# Power.net
KiCad netlist of a schematic drawn in Altium Designer
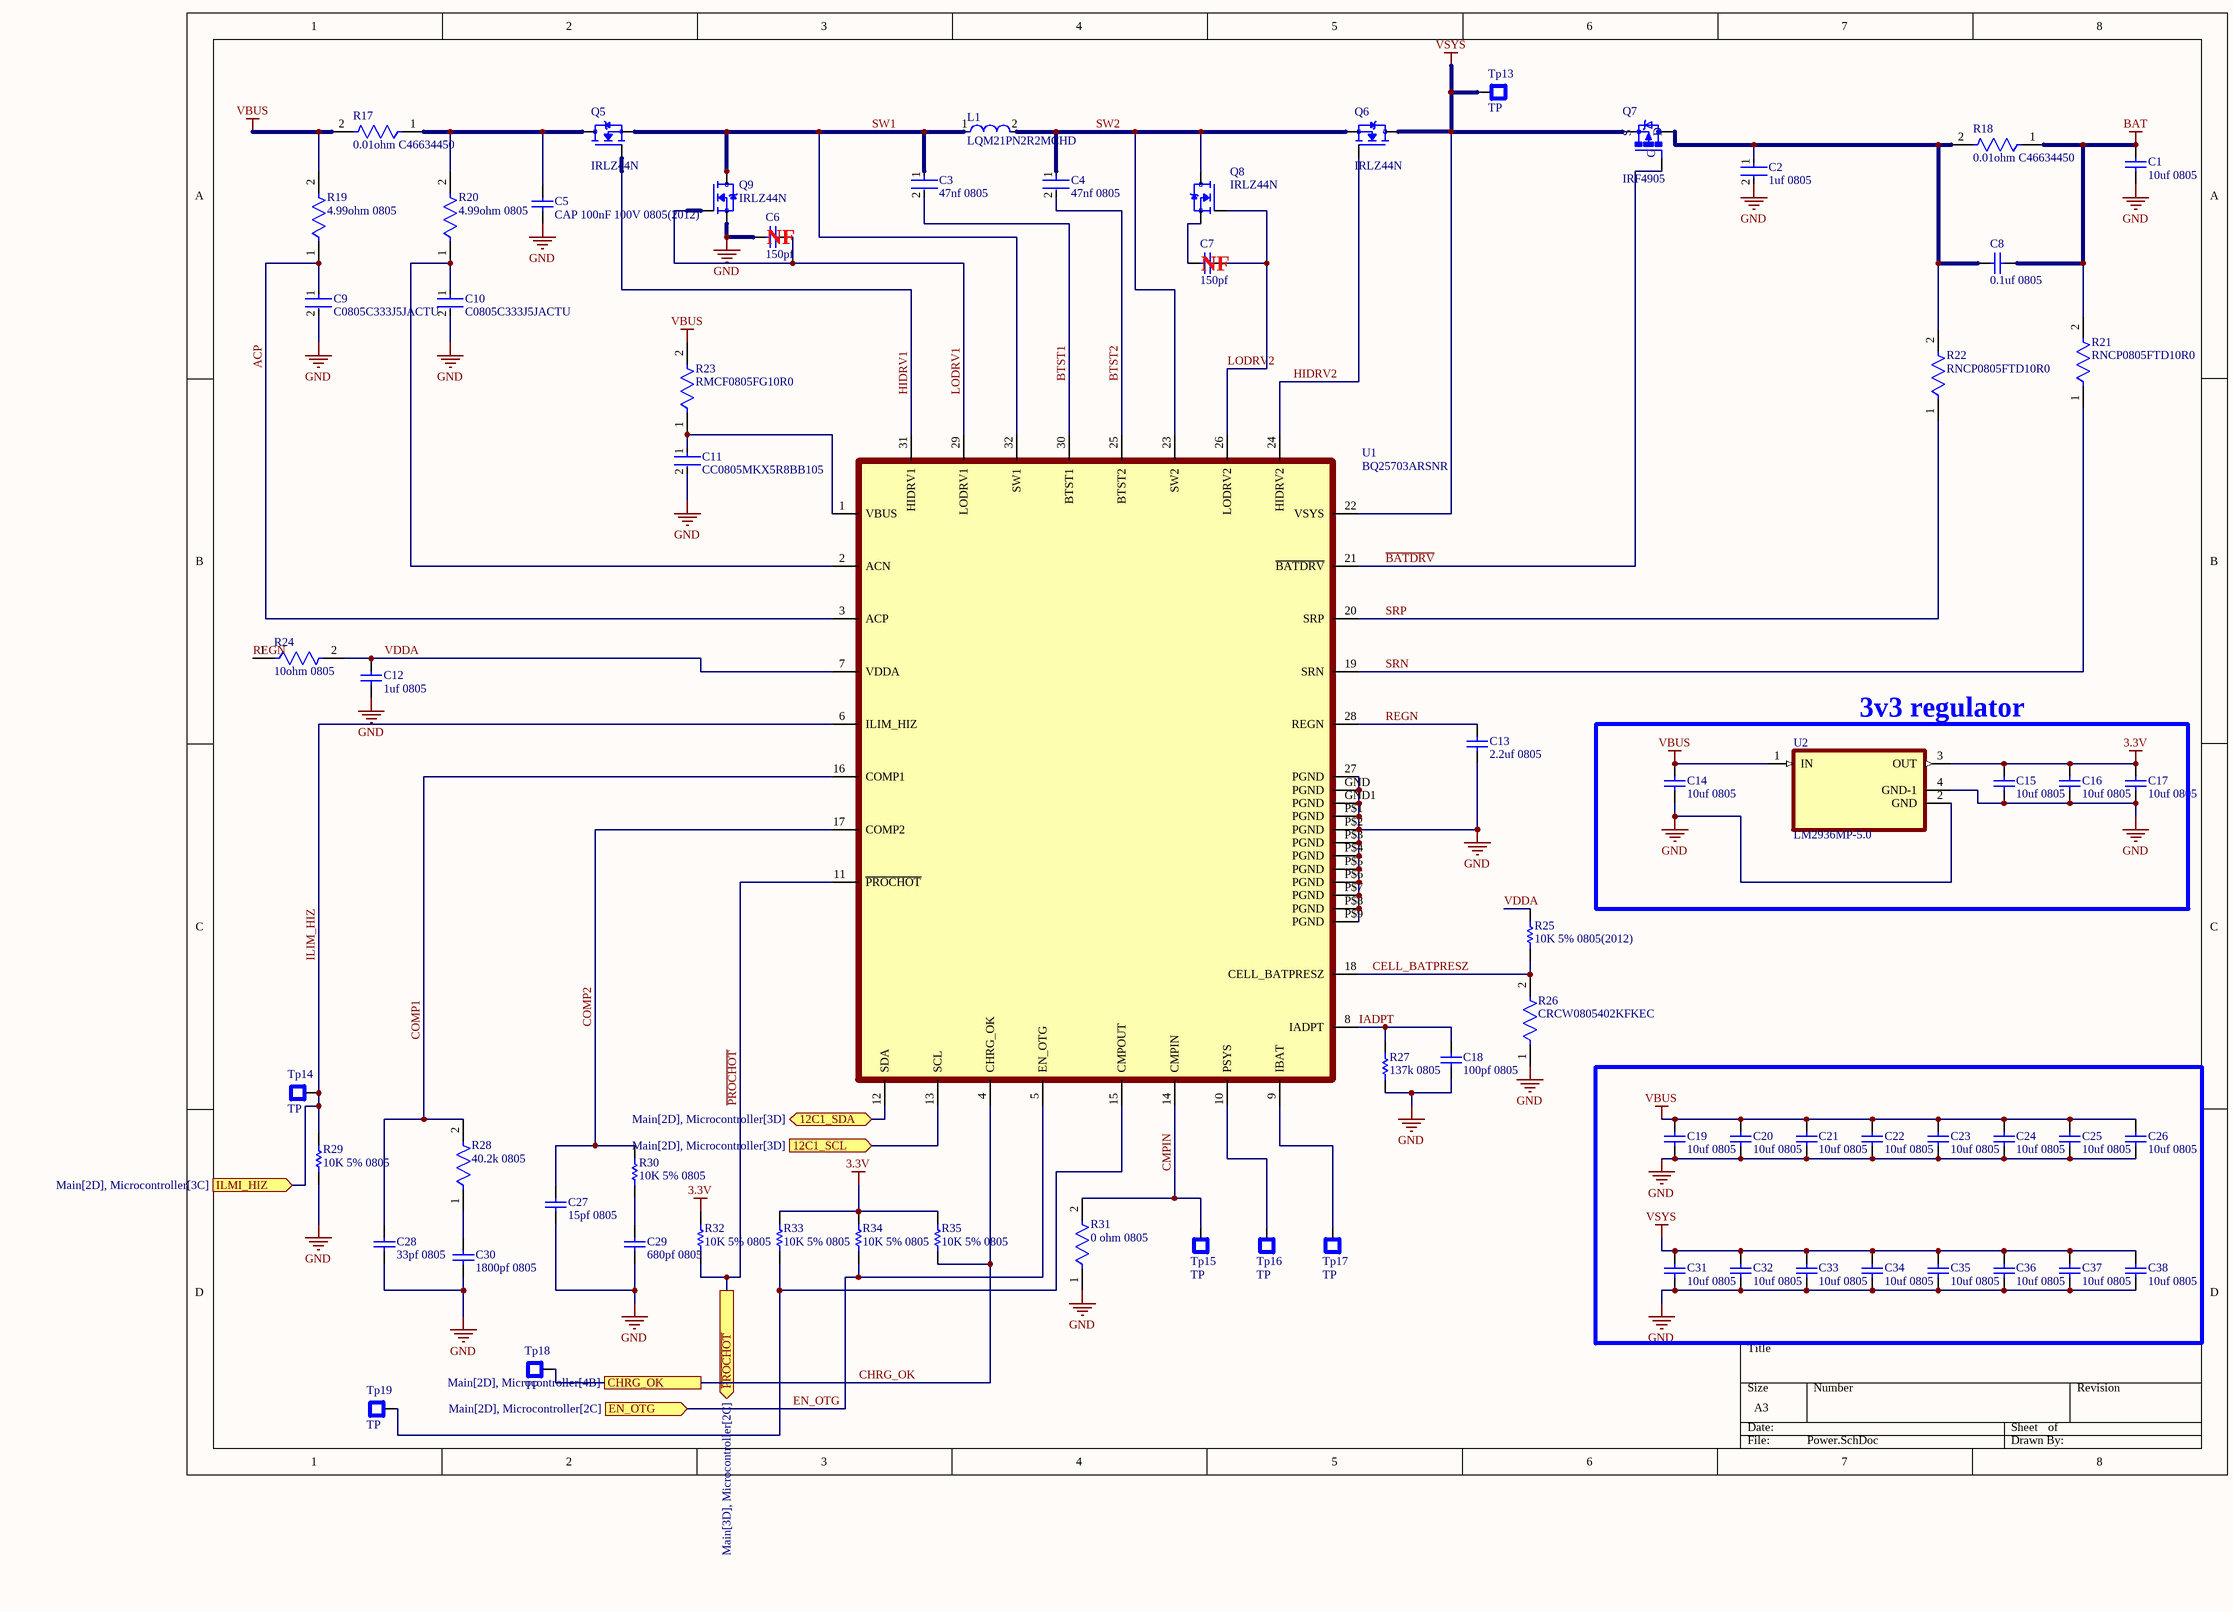
[diagram p0: Power.SchDoc]

(export (version "E")
  (design (tool "Eeschema 10.0.6"))
  (components
    (comp (ref "C1")
      (value "10uf 0805")
      (footprint "CAPC2013X140X50ML20T25")
      (fields
        (field (name "MANUFACTURER") "AVX Interconnect / Elco")
        (field (name "PART NUMBER") "0805ZC106KAT2A")
      )
      (libsource (lib "Altium Content Vault") (part "CAP"))
    )
    (comp (ref "C2")
      (value "1uf 0805")
      (footprint "FP-0805-L_2_01_0_2-W_1_25-MFG")
      (description "08051C105K4T2A Cap Ceramic 1uF 100V X7R 10% Pad SMD 0805 125C Automotive T/R")
      (fields (field (name "TOLERANCE") "10%"))
      (libsource (lib "Altium Content Vault") (part "b4654b650e69147ec39a6b967a45e02"))
    )
    (comp (ref "C3")
      (value "47nf 0805")
      (footprint "FP-C0805C-DN-MFG")
      (description "CAP CER 0.047UF 50V X7R 0805")
      (fields (field (name "TOLERANCE") "0.1") (field (name "MANUFACTURER") "KEMET"))
      (libsource (lib "Altium Content Vault") (part "b4654b650e69147ec39a6b967a45e02"))
    )
    (comp (ref "C4")
      (value "47nf 0805")
      (footprint "FP-C0805C-DN-MFG")
      (description "CAP CER 0.047UF 50V X7R 0805")
      (fields (field (name "TOLERANCE") "0.1") (field (name "MANUFACTURER") "KEMET"))
      (libsource (lib "Altium Content Vault") (part "b4654b650e69147ec39a6b967a45e02"))
    )
    (comp (ref "C5")
      (value "CAP 100nF 100V 0805(2012)")
      (footprint "CAPC0805(2012)145_M")
      (description "CAP 100nF 100V ±10% 0805 (2012 Metric) Thickness 1.45mm SMD")
      (fields (field (name "TOLERANCE") "Â±10%"))
      (libsource (lib "Altium Content Vault") (part "CAP"))
    )
    (comp (ref "C6")
      (value "150pf")
      (footprint "CAPC2013X145X48NL20T23")
      (fields (field (name "PART NUMBER") "VJ0805A151JXAMC") (field (name "MANUFACTURER") "Vitramon"))
      (libsource (lib "Altium Content Vault") (part "CAP"))
    )
    (comp (ref "C7")
      (value "150pf")
      (footprint "CAPC2013X145X48NL20T23")
      (fields (field (name "PART NUMBER") "VJ0805A151JXAMC") (field (name "MANUFACTURER") "Vitramon"))
      (libsource (lib "Altium Content Vault") (part "CAP"))
    )
    (comp (ref "C8")
      (value "0.1uf 0805")
      (footprint "CAPC2013X140X50ML20T25")
      (fields
        (field (name "PART NUMBER") "0805DD104KAT2A")
        (field (name "MANUFACTURER") "AVX Interconnect / Elco")
      )
      (libsource (lib "Altium Content Vault") (part "CAP"))
    )
    (comp (ref "C9")
      (value "C0805C333J5JACTU")
      (footprint "FP-C0805C-DN-MFG")
      (description "CAP CER 0.033UF 50V U2J 0805")
      (fields
        (field (name "MANUFACTURER") "KEMET")
        (field (name "OCTOPART") "https://octopart.com/c0805c333j5jactu-kemet-74774612")
      )
      (libsource (lib "Altium Content Vault") (part "b4654b650e69147ec39a6b967a45e02"))
    )
    (comp (ref "C10")
      (value "C0805C333J5JACTU")
      (footprint "FP-C0805C-DN-MFG")
      (description "CAP CER 0.033UF 50V U2J 0805")
      (fields
        (field (name "MANUFACTURER") "KEMET")
        (field (name "OCTOPART") "https://octopart.com/c0805c333j5jactu-kemet-74774612")
      )
      (libsource (lib "Altium Content Vault") (part "b4654b650e69147ec39a6b967a45e02"))
    )
    (comp (ref "C11")
      (value "CC0805MKX5R8BB105")
      (footprint "FP-CC0805-0_85-MFG")
      (description "CAP CER 1UF 25V X5R 0805")
      (fields
        (field (name "MANUFACTURER") "Yageo")
        (field (name "OCTOPART") "https://octopart.com/cc0805mkx5r8bb105-yageo-81932645")
      )
      (libsource (lib "Altium Content Vault") (part "11868f565c42a9108669ba33697ecf6"))
    )
    (comp (ref "C12")
      (value "1uf 0805")
      (footprint "CAPC2013X145X50NL20T20")
      (fields (field (name "PART NUMBER") "VJ0805Y105KXQRW1BC") (field (name "MANUFACTURER") "Vitramon"))
      (libsource (lib "Altium Content Vault") (part "CAP"))
    )
    (comp (ref "C13")
      (value "2.2uf 0805")
      (footprint "CAPC2013X100X50ML20T25")
      (fields (field (name "PART NUMBER") "C0805C225M4PACTU") (field (name "MANUFACTURER") "Kemet"))
      (libsource (lib "Altium Content Vault") (part "CAP"))
    )
    (comp (ref "C14")
      (value "10uf 0805")
      (footprint "CAPC2013X140X50ML20T25")
      (fields
        (field (name "MANUFACTURER") "AVX Interconnect / Elco")
        (field (name "PART NUMBER") "0805ZC106KAT2A")
      )
      (libsource (lib "Altium Content Vault") (part "CAP"))
    )
    (comp (ref "C15")
      (value "10uf 0805")
      (footprint "CAPC2013X140X50ML20T25")
      (fields
        (field (name "MANUFACTURER") "AVX Interconnect / Elco")
        (field (name "PART NUMBER") "0805ZC106KAT2A")
      )
      (libsource (lib "Altium Content Vault") (part "CAP"))
    )
    (comp (ref "C16")
      (value "10uf 0805")
      (footprint "CAPC2013X140X50ML20T25")
      (fields
        (field (name "MANUFACTURER") "AVX Interconnect / Elco")
        (field (name "PART NUMBER") "0805ZC106KAT2A")
      )
      (libsource (lib "Altium Content Vault") (part "CAP"))
    )
    (comp (ref "C17")
      (value "10uf 0805")
      (footprint "CAPC2013X140X50ML20T25")
      (fields
        (field (name "MANUFACTURER") "AVX Interconnect / Elco")
        (field (name "PART NUMBER") "0805ZC106KAT2A")
      )
      (libsource (lib "Altium Content Vault") (part "CAP"))
    )
    (comp (ref "C18")
      (value "100pf 0805")
      (footprint "CAPC2013X127X50NL20T25")
      (fields
        (field (name "PART NUMBER") "08052C101KAT2A")
        (field (name "MANUFACTURER") "AVX Interconnect / Elco")
      )
      (libsource (lib "Altium Content Vault") (part "CAP"))
    )
    (comp (ref "C19")
      (value "10uf 0805")
      (footprint "CAPC2013X140X50ML20T25")
      (fields
        (field (name "MANUFACTURER") "AVX Interconnect / Elco")
        (field (name "PART NUMBER") "0805ZC106KAT2A")
      )
      (libsource (lib "Altium Content Vault") (part "CAP"))
    )
    (comp (ref "C20")
      (value "10uf 0805")
      (footprint "CAPC2013X140X50ML20T25")
      (fields
        (field (name "MANUFACTURER") "AVX Interconnect / Elco")
        (field (name "PART NUMBER") "0805ZC106KAT2A")
      )
      (libsource (lib "Altium Content Vault") (part "CAP"))
    )
    (comp (ref "C21")
      (value "10uf 0805")
      (footprint "CAPC2013X140X50ML20T25")
      (fields
        (field (name "MANUFACTURER") "AVX Interconnect / Elco")
        (field (name "PART NUMBER") "0805ZC106KAT2A")
      )
      (libsource (lib "Altium Content Vault") (part "CAP"))
    )
    (comp (ref "C22")
      (value "10uf 0805")
      (footprint "CAPC2013X140X50ML20T25")
      (fields
        (field (name "MANUFACTURER") "AVX Interconnect / Elco")
        (field (name "PART NUMBER") "0805ZC106KAT2A")
      )
      (libsource (lib "Altium Content Vault") (part "CAP"))
    )
    (comp (ref "C23")
      (value "10uf 0805")
      (footprint "CAPC2013X140X50ML20T25")
      (fields
        (field (name "MANUFACTURER") "AVX Interconnect / Elco")
        (field (name "PART NUMBER") "0805ZC106KAT2A")
      )
      (libsource (lib "Altium Content Vault") (part "CAP"))
    )
    (comp (ref "C24")
      (value "10uf 0805")
      (footprint "CAPC2013X140X50ML20T25")
      (fields
        (field (name "MANUFACTURER") "AVX Interconnect / Elco")
        (field (name "PART NUMBER") "0805ZC106KAT2A")
      )
      (libsource (lib "Altium Content Vault") (part "CAP"))
    )
    (comp (ref "C25")
      (value "10uf 0805")
      (footprint "CAPC2013X140X50ML20T25")
      (fields
        (field (name "MANUFACTURER") "AVX Interconnect / Elco")
        (field (name "PART NUMBER") "0805ZC106KAT2A")
      )
      (libsource (lib "Altium Content Vault") (part "CAP"))
    )
    (comp (ref "C26")
      (value "10uf 0805")
      (footprint "CAPC2013X140X50ML20T25")
      (fields
        (field (name "MANUFACTURER") "AVX Interconnect / Elco")
        (field (name "PART NUMBER") "0805ZC106KAT2A")
      )
      (libsource (lib "Altium Content Vault") (part "CAP"))
    )
    (comp (ref "C27")
      (value "15pf 0805")
      (footprint "CAPC2013X94X50LL20T25")
      (fields
        (field (name "PART NUMBER") "08051A150KAT2A")
        (field (name "MANUFACTURER") "AVX Interconnect / Elco")
      )
      (libsource (lib "Altium Content Vault") (part "CAP"))
    )
    (comp (ref "C28")
      (value "33pf 0805")
      (footprint "CAPC2013X145X48LL20T23")
      (fields (field (name "PART NUMBER") "VJ0805A330JXBAC") (field (name "MANUFACTURER") "Vitramon"))
      (libsource (lib "Altium Content Vault") (part "CAP"))
    )
    (comp (ref "C29")
      (value "680pf 0805")
      (footprint "CAPC0805(2012)145_L")
      (description "CAP 680pF 100V ±10% 0805 (2012 Metric) Thickness 1.45mm SMD")
      (fields (field (name "TOLERANCE") "Â±10%"))
      (libsource (lib "Altium Content Vault") (part "CAP"))
    )
    (comp (ref "C30")
      (value "1800pf 0805")
      (footprint "CAPC2013X145X48ML20T23")
      (fields (field (name "PART NUMBER") "VJ0805A182FXAMT") (field (name "MANUFACTURER") "Vitramon"))
      (libsource (lib "Altium Content Vault") (part "CAP"))
    )
    (comp (ref "C31")
      (value "10uf 0805")
      (footprint "CAPC2013X140X50ML20T25")
      (fields
        (field (name "MANUFACTURER") "AVX Interconnect / Elco")
        (field (name "PART NUMBER") "0805ZC106KAT2A")
      )
      (libsource (lib "Altium Content Vault") (part "CAP"))
    )
    (comp (ref "C32")
      (value "10uf 0805")
      (footprint "CAPC2013X140X50ML20T25")
      (fields
        (field (name "MANUFACTURER") "AVX Interconnect / Elco")
        (field (name "PART NUMBER") "0805ZC106KAT2A")
      )
      (libsource (lib "Altium Content Vault") (part "CAP"))
    )
    (comp (ref "C33")
      (value "10uf 0805")
      (footprint "CAPC2013X140X50ML20T25")
      (fields
        (field (name "MANUFACTURER") "AVX Interconnect / Elco")
        (field (name "PART NUMBER") "0805ZC106KAT2A")
      )
      (libsource (lib "Altium Content Vault") (part "CAP"))
    )
    (comp (ref "C34")
      (value "10uf 0805")
      (footprint "CAPC2013X140X50ML20T25")
      (fields
        (field (name "MANUFACTURER") "AVX Interconnect / Elco")
        (field (name "PART NUMBER") "0805ZC106KAT2A")
      )
      (libsource (lib "Altium Content Vault") (part "CAP"))
    )
    (comp (ref "C35")
      (value "10uf 0805")
      (footprint "CAPC2013X140X50ML20T25")
      (fields
        (field (name "MANUFACTURER") "AVX Interconnect / Elco")
        (field (name "PART NUMBER") "0805ZC106KAT2A")
      )
      (libsource (lib "Altium Content Vault") (part "CAP"))
    )
    (comp (ref "C36")
      (value "10uf 0805")
      (footprint "CAPC2013X140X50ML20T25")
      (fields
        (field (name "MANUFACTURER") "AVX Interconnect / Elco")
        (field (name "PART NUMBER") "0805ZC106KAT2A")
      )
      (libsource (lib "Altium Content Vault") (part "CAP"))
    )
    (comp (ref "C37")
      (value "10uf 0805")
      (footprint "CAPC2013X140X50ML20T25")
      (fields
        (field (name "MANUFACTURER") "AVX Interconnect / Elco")
        (field (name "PART NUMBER") "0805ZC106KAT2A")
      )
      (libsource (lib "Altium Content Vault") (part "CAP"))
    )
    (comp (ref "C38")
      (value "10uf 0805")
      (footprint "CAPC2013X140X50ML20T25")
      (fields
        (field (name "MANUFACTURER") "AVX Interconnect / Elco")
        (field (name "PART NUMBER") "0805ZC106KAT2A")
      )
      (libsource (lib "Altium Content Vault") (part "CAP"))
    )
    (comp (ref "L1")
      (value "LQM21PN2R2MCHD")
      (footprint "FP-LQM21PN_CH-IPC_C")
      (description "Multilayer Type Inductor for Power Lines, 2012, 2.2μH, 20%, 0.25Ω, 1.3A")
      (libsource (lib "Altium Content Vault") (part "725321dda6339637d4d059423bc1c3c"))
    )
    (comp (ref "Q5")
      (value "IRLZ44N")
      (footprint "TO254P1054X469X1930-3")
      (description "N-Channel 55 V 47A (Tc) 3.8W (Ta), 110W (Tc) Surface Mount D2PAK")
      (fields (field (name "MF") "Infineon / IR"))
      (libsource (lib "power_schi") (part "IRLZ44N"))
    )
    (comp (ref "Q6")
      (value "IRLZ44N")
      (footprint "TO254P1054X469X1930-3")
      (description "N-Channel 55 V 47A (Tc) 3.8W (Ta), 110W (Tc) Surface Mount D2PAK")
      (fields (field (name "MF") "Infineon / IR"))
      (libsource (lib "power_schi") (part "IRLZ44N"))
    )
    (comp (ref "Q7")
      (value "IRF4905")
      (footprint "TO220BH")
      (description "P-Channel 55 V 74A (Tc) 200W (Tc) Through Hole TO-220AB")
      (fields (field (name "MF") "Infineon / IR"))
      (libsource (lib "power_schi") (part "IRF4905"))
    )
    (comp (ref "Q8")
      (value "IRLZ44N")
      (footprint "TO254P1054X469X1930-3")
      (description "N-Channel 55 V 47A (Tc) 3.8W (Ta), 110W (Tc) Surface Mount D2PAK")
      (fields (field (name "MF") "Infineon / IR"))
      (libsource (lib "power_schi") (part "IRLZ44N"))
    )
    (comp (ref "Q9")
      (value "IRLZ44N")
      (footprint "TO254P1054X469X1930-3")
      (description "N-Channel 55 V 47A (Tc) 3.8W (Ta), 110W (Tc) Surface Mount D2PAK")
      (fields (field (name "MF") "Infineon / IR"))
      (libsource (lib "power_schi") (part "IRLZ44N"))
    )
    (comp (ref "R17")
      (value "0.01ohm C46634450")
      (footprint "FP-CRCW0805-HPe3-MFG")
      (description "RES Thick Film, 4.99Ω, 0.5%, 0.5W, 100ppm/°C, 0805")
      (libsource (lib "Altium Content Vault") (part "1029c3af85768c4190bb7ad29bc67b5"))
    )
    (comp (ref "R18")
      (value "0.01ohm C46634450")
      (footprint "FP-CRCW0805-HPe3-MFG")
      (description "RES Thick Film, 4.99Ω, 0.5%, 0.5W, 100ppm/°C, 0805")
      (libsource (lib "Altium Content Vault") (part "1029c3af85768c4190bb7ad29bc67b5"))
    )
    (comp (ref "R19")
      (value "4.99ohm 0805")
      (footprint "FP-CRCW0805-HPe3-MFG")
      (description "RES Thick Film, 4.99Ω, 0.5%, 0.5W, 100ppm/°C, 0805")
      (libsource (lib "Altium Content Vault") (part "1029c3af85768c4190bb7ad29bc67b5"))
    )
    (comp (ref "R20")
      (value "4.99ohm 0805")
      (footprint "FP-CRCW0805-HPe3-MFG")
      (description "RES Thick Film, 4.99Ω, 0.5%, 0.5W, 100ppm/°C, 0805")
      (libsource (lib "Altium Content Vault") (part "1029c3af85768c4190bb7ad29bc67b5"))
    )
    (comp (ref "R21")
      (value "RNCP0805FTD10R0")
      (footprint "FP-RNCP0805-IPC_C")
      (description "10Ω ±1% 0.25W 0805 High Power Anti-Sulfur Thin Film Chip Resistor")
      (fields (field (name "TOLERANCE") "1%"))
      (libsource (lib "Altium Content Vault") (part "1029c3af85768c4190bb7ad29bc67b5"))
    )
    (comp (ref "R22")
      (value "RNCP0805FTD10R0")
      (footprint "FP-RNCP0805-IPC_C")
      (description "10Ω ±1% 0.25W 0805 High Power Anti-Sulfur Thin Film Chip Resistor")
      (fields (field (name "TOLERANCE") "1%"))
      (libsource (lib "Altium Content Vault") (part "1029c3af85768c4190bb7ad29bc67b5"))
    )
    (comp (ref "R23")
      (value "RMCF0805FG10R0")
      (footprint "FP-RMCF0805-IPC_B")
      (description "10Ω ±1% 0.125W 0805 Thick Film Chip Resistor AEC-Q200 compliant")
      (fields (field (name "TOLERANCE") "1%"))
      (libsource (lib "Altium Content Vault") (part "1029c3af85768c4190bb7ad29bc67b5"))
    )
    (comp (ref "R24")
      (value "10ohm 0805")
      (footprint "FP-RMCF0805-IPC_B")
      (description "10Ω ±1% 0.125W 0805 Thick Film Chip Resistor AEC-Q200 compliant")
      (fields (field (name "TOLERANCE") "1%"))
      (libsource (lib "Altium Content Vault") (part "1029c3af85768c4190bb7ad29bc67b5"))
    )
    (comp (ref "R25")
      (value "10K 5% 0805(2012)")
      (footprint "RESC0805(2012)_L")
      (description "10K 0.125W 5% 0805 (2012 Metric)  SMD")
      (fields (field (name "POWER") "0.125 W") (field (name "TOLERANCE") "5 %"))
      (libsource (lib "Altium Content Vault") (part "RES"))
    )
    (comp (ref "R26")
      (value "CRCW0805402KFKEC")
      (footprint "FP-CRCW0805-e3-IPC_B")
      (description "RES Thick Film, 402kΩ, 1%, 0.125W, 100ppm/°C, 0805")
      (fields (field (name "TOLERANCE") "1%"))
      (libsource (lib "Altium Content Vault") (part "1029c3af85768c4190bb7ad29bc67b5"))
    )
    (comp (ref "R27")
      (value "137k 0805")
      (footprint "RESC2013X60X35ML10T20")
      (fields (field (name "MANUFACTURER") "Yageo") (field (name "PART NUMBER") "RC0805FR-07137KL"))
      (libsource (lib "Altium Content Vault") (part "RES"))
    )
    (comp (ref "R28")
      (value "40.2k 0805")
      (footprint "FP-ESR10-MFG")
      (description "40.2kΩ ±1% 0.4W 0805 Anti-Surge Chip Resistor AEC-Q200")
      (fields (field (name "TOLERANCE") "1%"))
      (libsource (lib "Altium Content Vault") (part "1029c3af85768c4190bb7ad29bc67b5"))
    )
    (comp (ref "R29")
      (value "10K 5% 0805")
      (footprint "RESC0805(2012)_L")
      (description "10K 0.125W 5% 0805 (2012 Metric)  SMD")
      (fields (field (name "POWER") "0.125 W") (field (name "TOLERANCE") "5 %"))
      (libsource (lib "Altium Content Vault") (part "RES"))
    )
    (comp (ref "R30")
      (value "10K 5% 0805")
      (footprint "RESC0805(2012)_L")
      (description "10K 0.125W 5% 0805 (2012 Metric)  SMD")
      (fields (field (name "POWER") "0.125 W") (field (name "TOLERANCE") "5 %"))
      (libsource (lib "Altium Content Vault") (part "RES"))
    )
    (comp (ref "R31")
      (value "0 ohm 0805")
      (footprint "FP-HCJ0805-MFG")
      (description "RES 0 OHM JUMPER 1/2W 0805")
      (libsource (lib "Altium Content Vault") (part "1029c3af85768c4190bb7ad29bc67b5"))
    )
    (comp (ref "R32")
      (value "10K 5% 0805")
      (footprint "RESC0805(2012)_L")
      (description "10K 0.125W 5% 0805 (2012 Metric)  SMD")
      (fields (field (name "POWER") "0.125 W") (field (name "TOLERANCE") "5 %"))
      (libsource (lib "Altium Content Vault") (part "RES"))
    )
    (comp (ref "R33")
      (value "10K 5% 0805")
      (footprint "RESC0805(2012)_L")
      (description "10K 0.125W 5% 0805 (2012 Metric)  SMD")
      (fields (field (name "POWER") "0.125 W") (field (name "TOLERANCE") "5 %"))
      (libsource (lib "Altium Content Vault") (part "RES"))
    )
    (comp (ref "R34")
      (value "10K 5% 0805")
      (footprint "RESC0805(2012)_L")
      (description "10K 0.125W 5% 0805 (2012 Metric)  SMD")
      (fields (field (name "POWER") "0.125 W") (field (name "TOLERANCE") "5 %"))
      (libsource (lib "Altium Content Vault") (part "RES"))
    )
    (comp (ref "R35")
      (value "10K 5% 0805")
      (footprint "RESC0805(2012)_L")
      (description "10K 0.125W 5% 0805 (2012 Metric)  SMD")
      (fields (field (name "POWER") "0.125 W") (field (name "TOLERANCE") "5 %"))
      (libsource (lib "Altium Content Vault") (part "RES"))
    )
    (comp (ref "Tp13") (value "TP") (footprint "Tp") (libsource (lib "power_schi") (part "TP")))
    (comp (ref "Tp14") (value "TP") (footprint "Tp") (libsource (lib "power_schi") (part "TP")))
    (comp (ref "Tp15") (value "TP") (footprint "Tp") (libsource (lib "power_schi") (part "TP")))
    (comp (ref "Tp16") (value "TP") (footprint "Tp") (libsource (lib "power_schi") (part "TP")))
    (comp (ref "Tp17") (value "TP") (footprint "Tp") (libsource (lib "power_schi") (part "TP")))
    (comp (ref "Tp18") (value "TP") (footprint "Tp") (libsource (lib "power_schi") (part "TP")))
    (comp (ref "Tp19") (value "TP") (footprint "Tp") (libsource (lib "power_schi") (part "TP")))
    (comp (ref "U1")
      (value "BQ25703ARSNR")
      (footprint "BQ25703A_QFN-32")
      (description "MCU 32-bit ARM Cortex M0+ RISC 128KB Flash 1.8V/2.5V/3.3V 48-Pin LQFP Tray")
      (fields (field (name "MF") "Texas Instruments") (field (name "MANUFACTURER") "STMicroelectronics"))
      (libsource (lib "power_schi") (part "BQ25703ARSNR"))
    )
    (comp (ref "U2")
      (value "LM2936MP-5.0")
      (footprint "SOT230P700X180-4N")
      (fields (field (name "MF") "Texas Instruments"))
      (libsource (lib "power_schi") (part "LM2936MP-5.0"))
    )
  )
  (nets
    (net (code "1") (name "/12C1_SCL") (class "Default")
      (node (ref "U1") (pin "13") (pinfunction "SCL_13") (pintype "passive"))
    )
    (net (code "2") (name "/12C1_SDA") (class "Default")
      (node (ref "U1") (pin "12") (pinfunction "SDA_12") (pintype "passive"))
    )
    (net (code "3") (name "/ACP") (class "Default")
      (node (ref "C9") (pin "1") (pinfunction "1_1") (pintype "passive"))
      (node (ref "R19") (pin "1") (pinfunction "1_1") (pintype "passive"))
      (node (ref "U1") (pin "3") (pinfunction "ACP_3") (pintype "passive"))
    )
    (net (code "4") (name "/BTST1") (class "Default")
      (node (ref "C3") (pin "2") (pinfunction "2_2") (pintype "passive"))
      (node (ref "U1") (pin "30") (pinfunction "BTST1_30") (pintype "passive"))
    )
    (net (code "5") (name "/BTST2") (class "Default")
      (node (ref "C4") (pin "2") (pinfunction "2_2") (pintype "passive"))
      (node (ref "U1") (pin "25") (pinfunction "BTST2_25") (pintype "passive"))
    )
    (net (code "6") (name "/CELL_BATPRESZ") (class "Default")
      (node (ref "R25") (pin "1") (pinfunction "1_1") (pintype "passive"))
      (node (ref "R26") (pin "2") (pinfunction "2_2") (pintype "passive"))
      (node (ref "U1") (pin "18") (pinfunction "CELL_BATPRESZ_18") (pintype "passive"))
    )
    (net (code "7") (name "/CHRG_OK") (class "Default")
      (node (ref "R35") (pin "1") (pinfunction "1_1") (pintype "passive"))
      (node (ref "Tp18") (pin "1") (pinfunction "1_1") (pintype "passive"))
      (node (ref "U1") (pin "4") (pinfunction "CHRG_OK_4") (pintype "passive"))
    )
    (net (code "8") (name "/CMPIN") (class "Default")
      (node (ref "R31") (pin "2") (pinfunction "2_2") (pintype "passive"))
      (node (ref "Tp15") (pin "1") (pinfunction "1_1") (pintype "passive"))
      (node (ref "U1") (pin "14") (pinfunction "CMPIN_14") (pintype "passive"))
    )
    (net (code "9") (name "/COMP1") (class "Default")
      (node (ref "C28") (pin "2") (pinfunction "2_2") (pintype "passive"))
      (node (ref "R28") (pin "2") (pinfunction "2_2") (pintype "passive"))
      (node (ref "U1") (pin "16") (pinfunction "COMP1_16") (pintype "passive"))
    )
    (net (code "10") (name "/COMP2") (class "Default")
      (node (ref "C27") (pin "2") (pinfunction "2_2") (pintype "passive"))
      (node (ref "R30") (pin "2") (pinfunction "2_2") (pintype "passive"))
      (node (ref "U1") (pin "17") (pinfunction "COMP2_17") (pintype "passive"))
    )
    (net (code "11") (name "/EN_OTG") (class "Default")
      (node (ref "R34") (pin "1") (pinfunction "1_1") (pintype "passive"))
      (node (ref "U1") (pin "5") (pinfunction "EN_OTG_5") (pintype "passive"))
    )
    (net (code "12") (name "/HIDRV1") (class "Default")
      (node (ref "Q5") (pin "1") (pinfunction "G_1") (pintype "passive"))
      (node (ref "U1") (pin "31") (pinfunction "HIDRV1_31") (pintype "passive"))
    )
    (net (code "13") (name "/HIDRV2") (class "Default")
      (node (ref "Q6") (pin "1") (pinfunction "G_1") (pintype "passive"))
      (node (ref "U1") (pin "24") (pinfunction "HIDRV2_24") (pintype "passive"))
    )
    (net (code "14") (name "/IADPT") (class "Default")
      (node (ref "C18") (pin "2") (pinfunction "2_2") (pintype "passive"))
      (node (ref "R27") (pin "2") (pinfunction "2_2") (pintype "passive"))
      (node (ref "U1") (pin "8") (pinfunction "IADPT_8") (pintype "passive"))
    )
    (net (code "15") (name "/ILIM_HIZ") (class "Default")
      (node (ref "R29") (pin "2") (pinfunction "2_2") (pintype "passive"))
      (node (ref "Tp14") (pin "1") (pinfunction "1_1") (pintype "passive"))
      (node (ref "U1") (pin "6") (pinfunction "ILIM_HIZ_6") (pintype "passive"))
    )
    (net (code "16") (name "/LODRV1") (class "Default")
      (node (ref "C6") (pin "2") (pinfunction "2_2") (pintype "passive"))
      (node (ref "Q9") (pin "1") (pinfunction "G_1") (pintype "passive"))
      (node (ref "U1") (pin "29") (pinfunction "LODRV1_29") (pintype "passive"))
    )
    (net (code "17") (name "/LODRV2") (class "Default")
      (node (ref "C7") (pin "1") (pinfunction "1_1") (pintype "passive"))
      (node (ref "Q8") (pin "1") (pinfunction "G_1") (pintype "passive"))
      (node (ref "U1") (pin "26") (pinfunction "LODRV2_26") (pintype "passive"))
    )
    (net (code "18") (name "/REGN") (class "Default")
      (node (ref "C13") (pin "2") (pinfunction "2_2") (pintype "passive"))
      (node (ref "R24") (pin "1") (pinfunction "1_1") (pintype "passive"))
      (node (ref "U1") (pin "28") (pinfunction "REGN_28") (pintype "passive"))
    )
    (net (code "19") (name "/SRN") (class "Default")
      (node (ref "R21") (pin "1") (pinfunction "1_1") (pintype "passive"))
      (node (ref "U1") (pin "19") (pinfunction "SRN_19") (pintype "passive"))
    )
    (net (code "20") (name "/SRP") (class "Default")
      (node (ref "R22") (pin "1") (pinfunction "1_1") (pintype "passive"))
      (node (ref "U1") (pin "20") (pinfunction "SRP_20") (pintype "passive"))
    )
    (net (code "21") (name "/SW1") (class "Default")
      (node (ref "C3") (pin "1") (pinfunction "1_1") (pintype "passive"))
      (node (ref "L1") (pin "1") (pinfunction "1_1") (pintype "passive"))
      (node (ref "Q5") (pin "3") (pinfunction "S_3") (pintype "passive"))
      (node (ref "Q9") (pin "2") (pinfunction "D_2") (pintype "passive"))
      (node (ref "U1") (pin "32") (pinfunction "SW1_32") (pintype "passive"))
    )
    (net (code "22") (name "/SW2") (class "Default")
      (node (ref "C4") (pin "1") (pinfunction "1_1") (pintype "passive"))
      (node (ref "L1") (pin "2") (pinfunction "2_2") (pintype "passive"))
      (node (ref "Q6") (pin "3") (pinfunction "S_3") (pintype "passive"))
      (node (ref "Q8") (pin "2") (pinfunction "D_2") (pintype "passive"))
      (node (ref "U1") (pin "23") (pinfunction "SW2_23") (pintype "passive"))
    )
    (net (code "23") (name "/VDDA") (class "Default")
      (node (ref "C12") (pin "2") (pinfunction "2_2") (pintype "passive"))
      (node (ref "R24") (pin "2") (pinfunction "2_2") (pintype "passive"))
      (node (ref "R25") (pin "2") (pinfunction "2_2") (pintype "passive"))
      (node (ref "U1") (pin "7") (pinfunction "VDDA_7") (pintype "passive"))
    )
    (net (code "24") (name "/~{BATDRV}") (class "Default")
      (node (ref "Q7") (pin "G") (pinfunction "G_G") (pintype "passive"))
      (node (ref "U1") (pin "21") (pinfunction "~{BATDRV}_21") (pintype "passive"))
    )
    (net (code "25") (name "/~{PROCHOT}") (class "Default")
      (node (ref "R32") (pin "1") (pinfunction "1_1") (pintype "passive"))
      (node (ref "U1") (pin "11") (pinfunction "~{PROCHOT}_11") (pintype "passive"))
    )
    (net (code "26") (name "3.3V") (class "Default")
      (node (ref "C15") (pin "2") (pinfunction "2_2") (pintype "passive"))
      (node (ref "C16") (pin "2") (pinfunction "2_2") (pintype "passive"))
      (node (ref "C17") (pin "2") (pinfunction "2_2") (pintype "passive"))
      (node (ref "R32") (pin "2") (pinfunction "2_2") (pintype "passive"))
      (node (ref "R33") (pin "2") (pinfunction "2_2") (pintype "passive"))
      (node (ref "R34") (pin "2") (pinfunction "2_2") (pintype "passive"))
      (node (ref "R35") (pin "2") (pinfunction "2_2") (pintype "passive"))
      (node (ref "U2") (pin "3") (pinfunction "OUT_3") (pintype "output"))
    )
    (net (code "27") (name "BAT") (class "Default")
      (node (ref "C1") (pin "2") (pinfunction "2_2") (pintype "passive"))
      (node (ref "C8") (pin "1") (pinfunction "1_1") (pintype "passive"))
      (node (ref "R18") (pin "1") (pinfunction "1_1") (pintype "passive"))
      (node (ref "R21") (pin "2") (pinfunction "2_2") (pintype "passive"))
    )
    (net (code "28") (name "GND") (class "Default")
      (node (ref "C1") (pin "1") (pinfunction "1_1") (pintype "passive"))
      (node (ref "C10") (pin "2") (pinfunction "2_2") (pintype "passive"))
      (node (ref "C11") (pin "2") (pinfunction "2_2") (pintype "passive"))
      (node (ref "C12") (pin "1") (pinfunction "1_1") (pintype "passive"))
      (node (ref "C13") (pin "1") (pinfunction "1_1") (pintype "passive"))
      (node (ref "C14") (pin "1") (pinfunction "1_1") (pintype "passive"))
      (node (ref "C15") (pin "1") (pinfunction "1_1") (pintype "passive"))
      (node (ref "C16") (pin "1") (pinfunction "1_1") (pintype "passive"))
      (node (ref "C17") (pin "1") (pinfunction "1_1") (pintype "passive"))
      (node (ref "C18") (pin "1") (pinfunction "1_1") (pintype "passive"))
      (node (ref "C19") (pin "1") (pinfunction "1_1") (pintype "passive"))
      (node (ref "C2") (pin "2") (pinfunction "2_2") (pintype "passive"))
      (node (ref "C20") (pin "1") (pinfunction "1_1") (pintype "passive"))
      (node (ref "C21") (pin "1") (pinfunction "1_1") (pintype "passive"))
      (node (ref "C22") (pin "1") (pinfunction "1_1") (pintype "passive"))
      (node (ref "C23") (pin "1") (pinfunction "1_1") (pintype "passive"))
      (node (ref "C24") (pin "1") (pinfunction "1_1") (pintype "passive"))
      (node (ref "C25") (pin "1") (pinfunction "1_1") (pintype "passive"))
      (node (ref "C26") (pin "1") (pinfunction "1_1") (pintype "passive"))
      (node (ref "C27") (pin "1") (pinfunction "1_1") (pintype "passive"))
      (node (ref "C28") (pin "1") (pinfunction "1_1") (pintype "passive"))
      (node (ref "C29") (pin "1") (pinfunction "1_1") (pintype "passive"))
      (node (ref "C30") (pin "1") (pinfunction "1_1") (pintype "passive"))
      (node (ref "C31") (pin "1") (pinfunction "1_1") (pintype "passive"))
      (node (ref "C32") (pin "1") (pinfunction "1_1") (pintype "passive"))
      (node (ref "C33") (pin "1") (pinfunction "1_1") (pintype "passive"))
      (node (ref "C34") (pin "1") (pinfunction "1_1") (pintype "passive"))
      (node (ref "C35") (pin "1") (pinfunction "1_1") (pintype "passive"))
      (node (ref "C36") (pin "1") (pinfunction "1_1") (pintype "passive"))
      (node (ref "C37") (pin "1") (pinfunction "1_1") (pintype "passive"))
      (node (ref "C38") (pin "1") (pinfunction "1_1") (pintype "passive"))
      (node (ref "C5") (pin "1") (pinfunction "1_1") (pintype "passive"))
      (node (ref "C6") (pin "1") (pinfunction "1_1") (pintype "passive"))
      (node (ref "C9") (pin "2") (pinfunction "2_2") (pintype "passive"))
      (node (ref "Q9") (pin "3") (pinfunction "S_3") (pintype "passive"))
      (node (ref "R26") (pin "1") (pinfunction "1_1") (pintype "passive"))
      (node (ref "R27") (pin "1") (pinfunction "1_1") (pintype "passive"))
      (node (ref "R29") (pin "1") (pinfunction "1_1") (pintype "passive"))
      (node (ref "R31") (pin "1") (pinfunction "1_1") (pintype "passive"))
      (node (ref "U1") (pin "27") (pinfunction "PGND_27") (pintype "passive"))
      (node (ref "U1") (pin "GND") (pinfunction "PGND_GND") (pintype "passive"))
      (node (ref "U1") (pin "GND1") (pinfunction "PGND_GND1") (pintype "passive"))
      (node (ref "U1") (pin "P$1") (pinfunction "PGND_P$1") (pintype "passive"))
      (node (ref "U1") (pin "P$2") (pinfunction "PGND_P$2") (pintype "passive"))
      (node (ref "U1") (pin "P$3") (pinfunction "PGND_P$3") (pintype "passive"))
      (node (ref "U1") (pin "P$4") (pinfunction "PGND_P$4") (pintype "passive"))
      (node (ref "U1") (pin "P$5") (pinfunction "PGND_P$5") (pintype "passive"))
      (node (ref "U1") (pin "P$6") (pinfunction "PGND_P$6") (pintype "passive"))
      (node (ref "U1") (pin "P$7") (pinfunction "PGND_P$7") (pintype "passive"))
      (node (ref "U1") (pin "P$8") (pinfunction "PGND_P$8") (pintype "passive"))
      (node (ref "U1") (pin "P$9") (pinfunction "PGND_P$9") (pintype "passive"))
      (node (ref "U2") (pin "2") (pinfunction "GND_2") (pintype "power_in"))
      (node (ref "U2") (pin "4") (pinfunction "GND-1_4") (pintype "power_in"))
    )
    (net (code "29") (name "Net-(C2-Pad1)") (class "Default")
      (node (ref "C2") (pin "1") (pinfunction "1_1") (pintype "passive"))
      (node (ref "C8") (pin "2") (pinfunction "2_2") (pintype "passive"))
      (node (ref "Q7") (pin "D") (pinfunction "D_D") (pintype "passive"))
      (node (ref "R18") (pin "2") (pinfunction "2_2") (pintype "passive"))
      (node (ref "R22") (pin "2") (pinfunction "2_2") (pintype "passive"))
    )
    (net (code "30") (name "Net-(C29-Pad2)") (class "Default")
      (node (ref "C29") (pin "2") (pinfunction "2_2") (pintype "passive"))
      (node (ref "R30") (pin "1") (pinfunction "1_1") (pintype "passive"))
    )
    (net (code "31") (name "Net-(C30-Pad2)") (class "Default")
      (node (ref "C30") (pin "2") (pinfunction "2_2") (pintype "passive"))
      (node (ref "R28") (pin "1") (pinfunction "1_1") (pintype "passive"))
    )
    (net (code "32") (name "Net-(Q5-D)") (class "Default")
      (node (ref "C5") (pin "2") (pinfunction "2_2") (pintype "passive"))
      (node (ref "Q5") (pin "2") (pinfunction "D_2") (pintype "passive"))
      (node (ref "R17") (pin "1") (pinfunction "1_1") (pintype "passive"))
      (node (ref "R20") (pin "2") (pinfunction "2_2") (pintype "passive"))
    )
    (net (code "33") (name "Net-(Q8-S)") (class "Default")
      (node (ref "C7") (pin "2") (pinfunction "2_2") (pintype "passive"))
      (node (ref "Q8") (pin "3") (pinfunction "S_3") (pintype "passive"))
    )
    (net (code "34") (name "Net-(U1-ACN)") (class "Default")
      (node (ref "C10") (pin "1") (pinfunction "1_1") (pintype "passive"))
      (node (ref "R20") (pin "1") (pinfunction "1_1") (pintype "passive"))
      (node (ref "U1") (pin "2") (pinfunction "ACN_2") (pintype "passive"))
    )
    (net (code "35") (name "Net-(U1-CMPOUT)") (class "Default")
      (node (ref "R33") (pin "1") (pinfunction "1_1") (pintype "passive"))
      (node (ref "Tp19") (pin "1") (pinfunction "1_1") (pintype "passive"))
      (node (ref "U1") (pin "15") (pinfunction "CMPOUT_15") (pintype "passive"))
    )
    (net (code "36") (name "Net-(U1-IBAT)") (class "Default")
      (node (ref "Tp17") (pin "1") (pinfunction "1_1") (pintype "passive"))
      (node (ref "U1") (pin "9") (pinfunction "IBAT_9") (pintype "passive"))
    )
    (net (code "37") (name "Net-(U1-PSYS)") (class "Default")
      (node (ref "Tp16") (pin "1") (pinfunction "1_1") (pintype "passive"))
      (node (ref "U1") (pin "10") (pinfunction "PSYS_10") (pintype "passive"))
    )
    (net (code "38") (name "Net-(U1-VBUS)") (class "Default")
      (node (ref "C11") (pin "1") (pinfunction "1_1") (pintype "passive"))
      (node (ref "R23") (pin "1") (pinfunction "1_1") (pintype "passive"))
      (node (ref "U1") (pin "1") (pinfunction "VBUS_1") (pintype "passive"))
    )
    (net (code "39") (name "VBUS") (class "Default")
      (node (ref "C14") (pin "2") (pinfunction "2_2") (pintype "passive"))
      (node (ref "C19") (pin "2") (pinfunction "2_2") (pintype "passive"))
      (node (ref "C20") (pin "2") (pinfunction "2_2") (pintype "passive"))
      (node (ref "C21") (pin "2") (pinfunction "2_2") (pintype "passive"))
      (node (ref "C22") (pin "2") (pinfunction "2_2") (pintype "passive"))
      (node (ref "C23") (pin "2") (pinfunction "2_2") (pintype "passive"))
      (node (ref "C24") (pin "2") (pinfunction "2_2") (pintype "passive"))
      (node (ref "C25") (pin "2") (pinfunction "2_2") (pintype "passive"))
      (node (ref "C26") (pin "2") (pinfunction "2_2") (pintype "passive"))
      (node (ref "R17") (pin "2") (pinfunction "2_2") (pintype "passive"))
      (node (ref "R19") (pin "2") (pinfunction "2_2") (pintype "passive"))
      (node (ref "R23") (pin "2") (pinfunction "2_2") (pintype "passive"))
      (node (ref "U2") (pin "1") (pinfunction "IN_1") (pintype "input"))
    )
    (net (code "40") (name "VSYS") (class "Default")
      (node (ref "C31") (pin "2") (pinfunction "2_2") (pintype "passive"))
      (node (ref "C32") (pin "2") (pinfunction "2_2") (pintype "passive"))
      (node (ref "C33") (pin "2") (pinfunction "2_2") (pintype "passive"))
      (node (ref "C34") (pin "2") (pinfunction "2_2") (pintype "passive"))
      (node (ref "C35") (pin "2") (pinfunction "2_2") (pintype "passive"))
      (node (ref "C36") (pin "2") (pinfunction "2_2") (pintype "passive"))
      (node (ref "C37") (pin "2") (pinfunction "2_2") (pintype "passive"))
      (node (ref "C38") (pin "2") (pinfunction "2_2") (pintype "passive"))
      (node (ref "Q6") (pin "2") (pinfunction "D_2") (pintype "passive"))
      (node (ref "Q7") (pin "S") (pinfunction "S_S") (pintype "passive"))
      (node (ref "Tp13") (pin "1") (pinfunction "1_1") (pintype "passive"))
      (node (ref "U1") (pin "22") (pinfunction "VSYS_22") (pintype "passive"))
    )
  )
)
